# khoa_so_dien_tu.net
KiCad netlist of a schematic drawn in Altium Designer
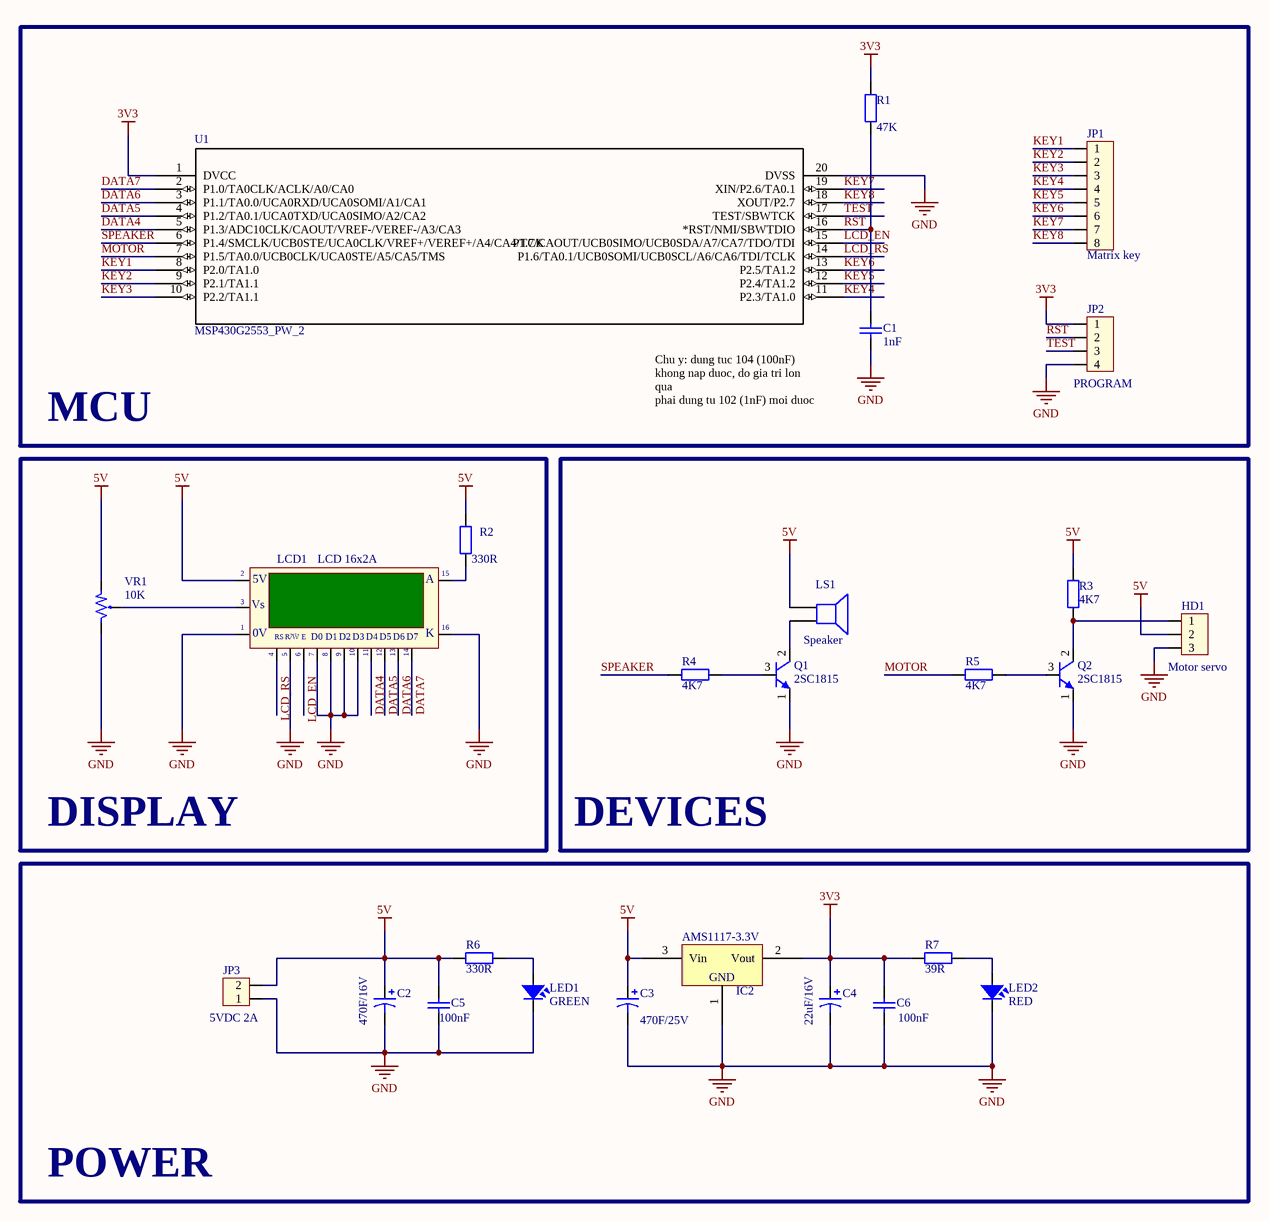
[diagram p0: khoa so dien tu.SchDoc]

(export (version "E")
  (design (tool "Eeschema 10.0.6"))
  (components
    (comp (ref "C1")
      (value "1nF")
      (footprint "Tu gom 104")
      (description "Capacitor")
      (fields (field (name "Comment") "Cap") (field (name "PUBLISHER") "Altium Limited"))
      (libsource (lib "Miscellaneous Devices") (part "Cap"))
    )
    (comp (ref "C2")
      (value "470F/16V")
      (footprint "CAP_470UF_16V")
      (description "Polarized Capacitor (Radial)")
      (fields (field (name "Comment") "Cap Pol1") (field (name "PUBLISHER") "Altium Limited"))
      (libsource (lib "Miscellaneous Devices") (part "Cap Pol1"))
    )
    (comp (ref "C3")
      (value "470F/25V")
      (footprint "CAP_470UF_25V")
      (description "Polarized Capacitor (Radial)")
      (fields (field (name "Comment") "Cap Pol1") (field (name "PUBLISHER") "Altium Limited"))
      (libsource (lib "Miscellaneous Devices") (part "Cap Pol1"))
    )
    (comp (ref "C4")
      (value "22uF/16V")
      (footprint "CAP_22UF_16V")
      (description "Polarized Capacitor (Radial)")
      (fields (field (name "Comment") "Cap Pol1") (field (name "PUBLISHER") "Altium Limited"))
      (libsource (lib "Miscellaneous Devices") (part "Cap Pol1"))
    )
    (comp (ref "C5")
      (value "100nF")
      (footprint "Tu gom 104")
      (description "Capacitor")
      (fields (field (name "Comment") "Cap") (field (name "PUBLISHER") "Altium Limited"))
      (libsource (lib "Miscellaneous Devices") (part "Cap"))
    )
    (comp (ref "C6")
      (value "100nF")
      (footprint "Tu gom 104")
      (description "Capacitor")
      (fields (field (name "Comment") "Cap") (field (name "PUBLISHER") "Altium Limited"))
      (libsource (lib "Miscellaneous Devices") (part "Cap"))
    )
    (comp (ref "HD1")
      (value "Motor servo")
      (footprint "Header_3")
      (description "Header 3 (Green)")
      (libsource (lib "lpson") (part "Hed3"))
    )
    (comp (ref "IC2")
      (value "AMS1117-3.3V")
      (footprint "AMS1117-3.3V")
      (libsource (lib "LuanVanPIR") (part "AMS1117"))
    )
    (comp (ref "JP1")
      (value "Matrix key")
      (footprint "Header_8")
      (description "Connector 8")
      (libsource (lib "lpson") (part "Con8"))
    )
    (comp (ref "JP2")
      (value "PROGRAM")
      (footprint "Header_4")
      (description "Connector 4")
      (libsource (lib "lpson") (part "Con4"))
    )
    (comp (ref "JP3")
      (value "5VDC 2A")
      (footprint "CON2")
      (description "Connector 2")
      (libsource (lib "lpson") (part "Con2"))
    )
    (comp (ref "LCD1")
      (value "LCD 16x2A")
      (footprint "LCD16x2")
      (description "LCD dipslay 16 char, 2 line")
      (libsource (lib "VNELEK") (part "LCD16x2A"))
    )
    (comp (ref "LED1")
      (value "GREEN")
      (footprint "LED3G")
      (description "LED Single colour Green and Red")
      (libsource (lib "VNELEK") (part "LED"))
    )
    (comp (ref "LED2")
      (value "RED")
      (footprint "LED3R")
      (description "LED Single colour Green and Red")
      (libsource (lib "VNELEK") (part "LED"))
    )
    (comp (ref "LS1")
      (value "Speaker")
      (footprint "SPEAKER")
      (description "Loudspeaker")
      (fields (field (name "PUBLISHER") "Altium Limited"))
      (libsource (lib "Miscellaneous Devices") (part "Speaker"))
    )
    (comp (ref "Q1")
      (value "2SC1815")
      (footprint "2SC1815")
      (description "Trans NPN 50V 150mA TO-92")
      (libsource (lib "lpson") (part "2SC1815"))
    )
    (comp (ref "Q2")
      (value "2SC1815")
      (footprint "2SC1815")
      (description "Trans NPN 50V 150mA TO-92")
      (libsource (lib "lpson") (part "2SC1815"))
    )
    (comp (ref "R1")
      (value "47K")
      (footprint "RES 1/4W CFR25")
      (description "Resistor")
      (fields (field (name "Comment") "Res2") (field (name "PUBLISHER") "Altium Limited"))
      (libsource (lib "Miscellaneous Devices") (part "Res2"))
    )
    (comp (ref "R2")
      (value "330R")
      (footprint "RES 1/4W CFR25")
      (description "Resistor")
      (fields (field (name "Comment") "Res2") (field (name "PUBLISHER") "Altium Limited"))
      (libsource (lib "Miscellaneous Devices") (part "Res2"))
    )
    (comp (ref "R3")
      (value "4K7")
      (footprint "RES 1/4W CFR25")
      (description "Resistor")
      (fields (field (name "Comment") "Res2") (field (name "PUBLISHER") "Altium Limited"))
      (libsource (lib "Miscellaneous Devices") (part "Res2"))
    )
    (comp (ref "R4")
      (value "4K7")
      (footprint "RES 1/4W CFR25")
      (description "Resistor")
      (fields (field (name "Comment") "Res2") (field (name "PUBLISHER") "Altium Limited"))
      (libsource (lib "") (part "Res2_1"))
    )
    (comp (ref "R5")
      (value "4K7")
      (footprint "RES 1/4W CFR25")
      (description "Resistor")
      (fields (field (name "Comment") "Res2") (field (name "PUBLISHER") "Altium Limited"))
      (libsource (lib "") (part "Res2_1"))
    )
    (comp (ref "R6")
      (value "330R")
      (footprint "RES 1/4W CFR25")
      (description "Resistor")
      (fields (field (name "Comment") "Res2") (field (name "PUBLISHER") "Altium Limited"))
      (libsource (lib "") (part "Res2_2"))
    )
    (comp (ref "R7")
      (value "39R")
      (footprint "RES 1/4W CFR25")
      (description "Resistor")
      (fields (field (name "Comment") "Res2") (field (name "PUBLISHER") "Altium Limited"))
      (libsource (lib "") (part "Res2_2"))
    )
    (comp (ref "U1")
      (value "MSP430G2553_PW_2")
      (footprint "MSP430G2553")
      (description "Imported")
      (fields
        (field (name "MANUFACTURER_PART_NUMBER") "msp430g2553_pw_20")
        (field (name "GENERIC_PART_NUMBER") "MSP430G2553")
      )
      (libsource (lib "MSP430G2553_PW_2") (part "MSP430G2553_PW_2"))
    )
    (comp (ref "VR1")
      (value "10K")
      (footprint "VR1")
      (description "Var Resistor")
      (libsource (lib "VNELEK") (part "VR1"))
    )
  )
  (nets
    (net (code "1") (name "/DATA4") (class "Default")
      (node (ref "LCD1") (pin "11") (pinfunction "D4_11") (pintype "passive"))
      (node (ref "U1") (pin "5") (pinfunction "P1.3/ADC10CLK/CAOUT/VREF-/VEREF-/A3/CA3_5") (pintype "bidirectional"))
    )
    (net (code "2") (name "/DATA5") (class "Default")
      (node (ref "LCD1") (pin "12") (pinfunction "D5_12") (pintype "passive"))
      (node (ref "U1") (pin "4") (pinfunction "P1.2/TA0.1/UCA0TXD/UCA0SIMO/A2/CA2_4") (pintype "bidirectional"))
    )
    (net (code "3") (name "/DATA6") (class "Default")
      (node (ref "LCD1") (pin "13") (pinfunction "D6_13") (pintype "passive"))
      (node (ref "U1") (pin "3") (pinfunction "P1.1/TA0.0/UCA0RXD/UCA0SOMI/A1/CA1_3") (pintype "bidirectional"))
    )
    (net (code "4") (name "/DATA7") (class "Default")
      (node (ref "LCD1") (pin "14") (pinfunction "D7_14") (pintype "passive"))
      (node (ref "U1") (pin "2") (pinfunction "P1.0/TA0CLK/ACLK/A0/CA0_2") (pintype "bidirectional"))
    )
    (net (code "5") (name "/KEY1") (class "Default")
      (node (ref "JP1") (pin "1") (pinfunction "1_1") (pintype "passive"))
      (node (ref "U1") (pin "8") (pinfunction "P2.0/TA1.0_8") (pintype "bidirectional"))
    )
    (net (code "6") (name "/KEY2") (class "Default")
      (node (ref "JP1") (pin "2") (pinfunction "2_2") (pintype "passive"))
      (node (ref "U1") (pin "9") (pinfunction "P2.1/TA1.1_9") (pintype "bidirectional"))
    )
    (net (code "7") (name "/KEY3") (class "Default")
      (node (ref "JP1") (pin "3") (pinfunction "3_3") (pintype "passive"))
      (node (ref "U1") (pin "10") (pinfunction "P2.2/TA1.1_10") (pintype "bidirectional"))
    )
    (net (code "8") (name "/KEY4") (class "Default")
      (node (ref "JP1") (pin "4") (pinfunction "4_4") (pintype "passive"))
      (node (ref "U1") (pin "11") (pinfunction "P2.3/TA1.0_11") (pintype "bidirectional"))
    )
    (net (code "9") (name "/KEY5") (class "Default")
      (node (ref "JP1") (pin "5") (pinfunction "5_5") (pintype "passive"))
      (node (ref "U1") (pin "12") (pinfunction "P2.4/TA1.2_12") (pintype "bidirectional"))
    )
    (net (code "10") (name "/KEY6") (class "Default")
      (node (ref "JP1") (pin "6") (pinfunction "6_6") (pintype "passive"))
      (node (ref "U1") (pin "13") (pinfunction "P2.5/TA1.2_13") (pintype "bidirectional"))
    )
    (net (code "11") (name "/KEY7") (class "Default")
      (node (ref "JP1") (pin "7") (pinfunction "7_7") (pintype "passive"))
      (node (ref "U1") (pin "19") (pinfunction "XIN/P2.6/TA0.1_19") (pintype "bidirectional"))
    )
    (net (code "12") (name "/KEY8") (class "Default")
      (node (ref "JP1") (pin "8") (pinfunction "8_8") (pintype "passive"))
      (node (ref "U1") (pin "18") (pinfunction "XOUT/P2.7_18") (pintype "bidirectional"))
    )
    (net (code "13") (name "/LCD_EN") (class "Default")
      (node (ref "LCD1") (pin "6") (pinfunction "~{EN}_6") (pintype "passive"))
      (node (ref "U1") (pin "15") (pinfunction "P1.7/CAOUT/UCB0SIMO/UCB0SDA/A7/CA7/TDO/TDI_15") (pintype "bidirectional"))
    )
    (net (code "14") (name "/LCD_RS") (class "Default")
      (node (ref "LCD1") (pin "4") (pinfunction "RS_4") (pintype "passive"))
      (node (ref "U1") (pin "14") (pinfunction "P1.6/TA0.1/UCB0SOMI/UCB0SCL/A6/CA6/TDI/TCLK_14") (pintype "bidirectional"))
    )
    (net (code "15") (name "/MOTOR") (class "Default")
      (node (ref "R5") (pin "1") (pinfunction "1_1") (pintype "passive"))
      (node (ref "U1") (pin "7") (pinfunction "P1.5/TA0.0/UCB0CLK/UCA0STE/A5/CA5/TMS_7") (pintype "bidirectional"))
    )
    (net (code "16") (name "/RST") (class "Default")
      (node (ref "C1") (pin "1") (pinfunction "1_1") (pintype "passive"))
      (node (ref "JP2") (pin "2") (pinfunction "2_2") (pintype "passive"))
      (node (ref "R1") (pin "1") (pinfunction "1_1") (pintype "passive"))
      (node (ref "U1") (pin "16") (pinfunction "*RST/NMI/SBWTDIO_16") (pintype "bidirectional"))
    )
    (net (code "17") (name "/SPEAKER") (class "Default")
      (node (ref "R4") (pin "1") (pinfunction "1_1") (pintype "passive"))
      (node (ref "U1") (pin "6") (pinfunction "P1.4/SMCLK/UCB0STE/UCA0CLK/VREF+/VEREF+/A4/CA4/TCK_6") (pintype "bidirectional"))
    )
    (net (code "18") (name "/TEST") (class "Default")
      (node (ref "JP2") (pin "3") (pinfunction "3_3") (pintype "passive"))
      (node (ref "U1") (pin "17") (pinfunction "TEST/SBWTCK_17") (pintype "bidirectional"))
    )
    (net (code "19") (name "3V3") (class "Default")
      (node (ref "C4") (pin "1") (pinfunction "1_1") (pintype "passive"))
      (node (ref "C6") (pin "2") (pinfunction "2_2") (pintype "passive"))
      (node (ref "IC2") (pin "2") (pinfunction "Vout_2") (pintype "passive"))
      (node (ref "JP2") (pin "1") (pinfunction "1_1") (pintype "passive"))
      (node (ref "R1") (pin "2") (pinfunction "2_2") (pintype "passive"))
      (node (ref "R7") (pin "2") (pinfunction "2_2") (pintype "passive"))
      (node (ref "U1") (pin "1") (pinfunction "DVCC_1") (pintype "power_in"))
    )
    (net (code "20") (name "5V") (class "Default")
      (node (ref "C2") (pin "1") (pinfunction "1_1") (pintype "passive"))
      (node (ref "C3") (pin "1") (pinfunction "1_1") (pintype "passive"))
      (node (ref "C5") (pin "2") (pinfunction "2_2") (pintype "passive"))
      (node (ref "HD1") (pin "2") (pinfunction "2_2") (pintype "passive"))
      (node (ref "IC2") (pin "3") (pinfunction "Vin_3") (pintype "passive"))
      (node (ref "JP3") (pin "2") (pinfunction "2_2") (pintype "passive"))
      (node (ref "LCD1") (pin "2") (pinfunction "VDD_2") (pintype "passive"))
      (node (ref "LS1") (pin "2") (pinfunction "2_2") (pintype "passive"))
      (node (ref "R2") (pin "2") (pinfunction "2_2") (pintype "passive"))
      (node (ref "R3") (pin "2") (pinfunction "2_2") (pintype "passive"))
      (node (ref "R6") (pin "2") (pinfunction "2_2") (pintype "passive"))
      (node (ref "VR1") (pin "1") (pinfunction "1_1") (pintype "passive"))
    )
    (net (code "21") (name "GND") (class "Default")
      (node (ref "C1") (pin "2") (pinfunction "2_2") (pintype "passive"))
      (node (ref "C2") (pin "2") (pinfunction "2_2") (pintype "passive"))
      (node (ref "C3") (pin "2") (pinfunction "2_2") (pintype "passive"))
      (node (ref "C4") (pin "2") (pinfunction "2_2") (pintype "passive"))
      (node (ref "C5") (pin "1") (pinfunction "1_1") (pintype "passive"))
      (node (ref "C6") (pin "1") (pinfunction "1_1") (pintype "passive"))
      (node (ref "HD1") (pin "3") (pinfunction "3_3") (pintype "passive"))
      (node (ref "IC2") (pin "1") (pinfunction "GND_1") (pintype "passive"))
      (node (ref "JP2") (pin "4") (pinfunction "4_4") (pintype "passive"))
      (node (ref "JP3") (pin "1") (pinfunction "1_1") (pintype "passive"))
      (node (ref "LCD1") (pin "1") (pinfunction "GND_1") (pintype "passive"))
      (node (ref "LCD1") (pin "10") (pinfunction "D3_10") (pintype "passive"))
      (node (ref "LCD1") (pin "16") (pinfunction "K_16") (pintype "passive"))
      (node (ref "LCD1") (pin "5") (pinfunction "R/~{W}_5") (pintype "passive"))
      (node (ref "LCD1") (pin "7") (pinfunction "D0_7") (pintype "passive"))
      (node (ref "LCD1") (pin "8") (pinfunction "D1_8") (pintype "passive"))
      (node (ref "LCD1") (pin "9") (pinfunction "D2_9") (pintype "passive"))
      (node (ref "LED1") (pin "2") (pinfunction "2_2") (pintype "passive"))
      (node (ref "LED2") (pin "2") (pinfunction "2_2") (pintype "passive"))
      (node (ref "Q1") (pin "1") (pinfunction "E_1") (pintype "passive"))
      (node (ref "Q2") (pin "1") (pinfunction "E_1") (pintype "passive"))
      (node (ref "U1") (pin "20") (pinfunction "DVSS_20") (pintype "power_in"))
      (node (ref "VR1") (pin "3") (pinfunction "3_3") (pintype "passive"))
    )
    (net (code "22") (name "Net-(LCD1-A)") (class "Default")
      (node (ref "LCD1") (pin "15") (pinfunction "A_15") (pintype "passive"))
      (node (ref "R2") (pin "1") (pinfunction "1_1") (pintype "passive"))
    )
    (net (code "23") (name "Net-(LCD1-VEE)") (class "Default")
      (node (ref "LCD1") (pin "3") (pinfunction "VEE_3") (pintype "passive"))
      (node (ref "VR1") (pin "2") (pinfunction "2_2") (pintype "passive"))
    )
    (net (code "24") (name "Net-(LED1-Pad1)") (class "Default")
      (node (ref "LED1") (pin "1") (pinfunction "1_1") (pintype "passive"))
      (node (ref "R6") (pin "1") (pinfunction "1_1") (pintype "passive"))
    )
    (net (code "25") (name "Net-(LED2-Pad1)") (class "Default")
      (node (ref "LED2") (pin "1") (pinfunction "1_1") (pintype "passive"))
      (node (ref "R7") (pin "1") (pinfunction "1_1") (pintype "passive"))
    )
    (net (code "26") (name "Net-(Q1-B)") (class "Default")
      (node (ref "Q1") (pin "3") (pinfunction "B_3") (pintype "passive"))
      (node (ref "R4") (pin "2") (pinfunction "2_2") (pintype "passive"))
    )
    (net (code "27") (name "Net-(Q1-C)") (class "Default")
      (node (ref "LS1") (pin "1") (pinfunction "1_1") (pintype "passive"))
      (node (ref "Q1") (pin "2") (pinfunction "C_2") (pintype "passive"))
    )
    (net (code "28") (name "Net-(Q2-B)") (class "Default")
      (node (ref "Q2") (pin "3") (pinfunction "B_3") (pintype "passive"))
      (node (ref "R5") (pin "2") (pinfunction "2_2") (pintype "passive"))
    )
    (net (code "29") (name "Net-(Q2-C)") (class "Default")
      (node (ref "HD1") (pin "1") (pinfunction "1_1") (pintype "passive"))
      (node (ref "Q2") (pin "2") (pinfunction "C_2") (pintype "passive"))
      (node (ref "R3") (pin "1") (pinfunction "1_1") (pintype "passive"))
    )
  )
)
